# CANTransceiver.net
KiCad netlist of a schematic drawn in Altium Designer
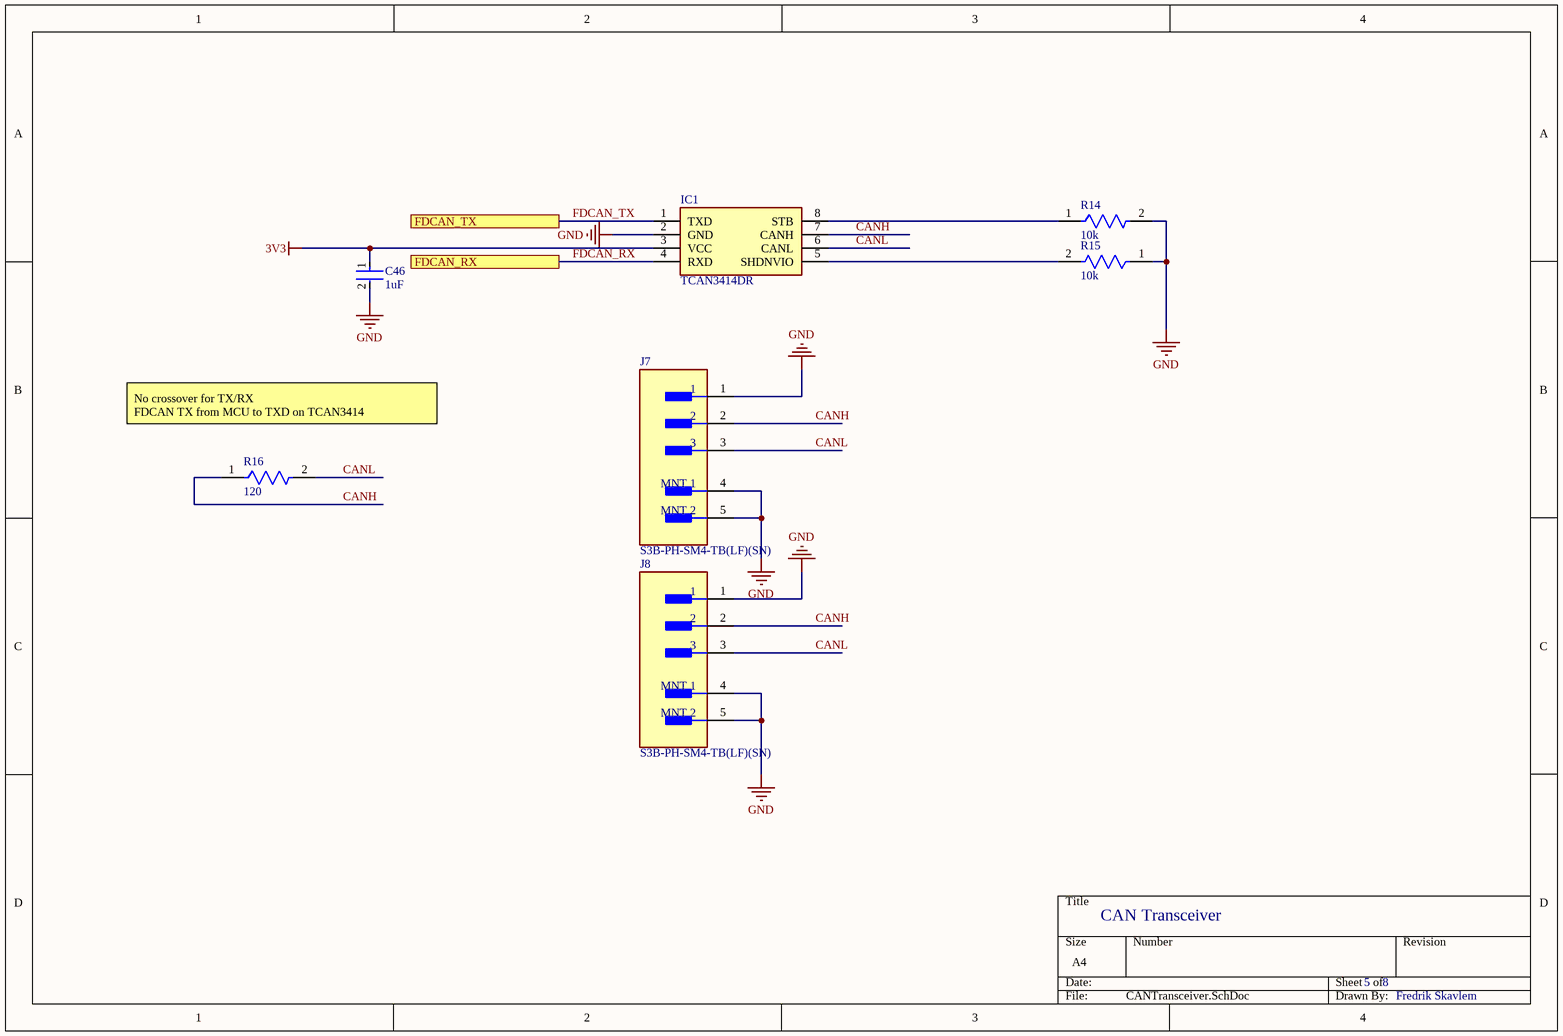
[diagram p0: CANTransceiver.SchDoc]

(export (version "E")
  (design (tool "Eeschema 10.0.6"))
  (components
    (comp (ref "C46")
      (value "1uF")
      (footprint "FP-CL10-IPC_C")
      (description "Cap Ceramic 1uF 16V X7R ±10% Pad SMD 0603 +125°C T/R\r\nCL10B105KO8NNNL")
      (fields (field (name "TOLERANCE") "10%"))
      (libsource (lib "Altium Content Vault") (part "b4654b650e69147ec39a6b967a45e02"))
    )
    (comp (ref "IC1")
      (value "TCAN3414DR")
      (footprint "SamacSys:SOIC127P600X175-8N")
      (description "Integrated Circuit")
      (fields (field (name "MOUSER PART NUMBER") "595-TCAN3414DR"))
      (libsource (lib "*") (part "TCAN3414DR"))
    )
    (comp (ref "J7")
      (value "S3B-PH-SM4-TB(LF)(SN)")
      (footprint "FP-S3B-PH-SM4-TB_LF_SN-MFG")
      (description "Connector Header, PH Series, 3 Position, Side Entry, 2.00mm, Solder, Surface Mount, Natural.")
      (libsource (lib "UiS Aerospace") (part "38689d6f3df0f9b234c6ddcef280d85"))
    )
    (comp (ref "J8")
      (value "S3B-PH-SM4-TB(LF)(SN)")
      (footprint "FP-S3B-PH-SM4-TB_LF_SN-MFG")
      (description "Connector Header, PH Series, 3 Position, Side Entry, 2.00mm, Solder, Surface Mount, Natural.")
      (libsource (lib "UiS Aerospace") (part "38689d6f3df0f9b234c6ddcef280d85"))
    )
    (comp (ref "R14")
      (value "10k")
      (footprint "FP-RT0603-IPC_C")
      (description "RES SMD 10K OHM 1% 1/10W 0603\r\nRT0603FRE0710KL")
      (fields
        (field (name "MANUFACTURER") "Yageo")
        (field (name "OCTOPART") "https://octopart.com/rt0603fre0710kl-yageo-40009243")
      )
      (libsource (lib "Altium Content Vault") (part "1029c3af85768c4190bb7ad29bc67b5"))
    )
    (comp (ref "R15")
      (value "10k")
      (footprint "FP-RT0603-IPC_C")
      (description "RES SMD 10K OHM 1% 1/10W 0603\r\nRT0603FRE0710KL")
      (fields
        (field (name "MANUFACTURER") "Yageo")
        (field (name "OCTOPART") "https://octopart.com/rt0603fre0710kl-yageo-40009243")
      )
      (libsource (lib "Altium Content Vault") (part "1029c3af85768c4190bb7ad29bc67b5"))
    )
    (comp (ref "R16")
      (value "120")
      (footprint "FP-AF0603-IPC_C")
      (description "Anti-Sulfurated Chip Resistors Automotive Grade 120Ω 1% 100ppm/°C 0603 AF0603FR-07120RL")
      (fields (field (name "TOLERANCE") "1%"))
      (libsource (lib "Altium Content Vault") (part "1029c3af85768c4190bb7ad29bc67b5"))
    )
  )
  (nets
    (net (code "1") (name "/CANH") (class "Default")
      (node (ref "IC1") (pin "7") (pinfunction "CANH_7") (pintype "passive"))
      (node (ref "J7") (pin "2") (pinfunction "2_2") (pintype "passive"))
      (node (ref "J8") (pin "2") (pinfunction "2_2") (pintype "passive"))
      (node (ref "R16") (pin "1") (pinfunction "1_1") (pintype "passive"))
    )
    (net (code "2") (name "/CANL") (class "Default")
      (node (ref "IC1") (pin "6") (pinfunction "CANL_6") (pintype "passive"))
      (node (ref "J7") (pin "3") (pinfunction "3_3") (pintype "passive"))
      (node (ref "J8") (pin "3") (pinfunction "3_3") (pintype "passive"))
      (node (ref "R16") (pin "2") (pinfunction "2_2") (pintype "passive"))
    )
    (net (code "3") (name "/FDCAN_RX") (class "Default")
      (node (ref "IC1") (pin "4") (pinfunction "RXD_4") (pintype "passive"))
    )
    (net (code "4") (name "/FDCAN_TX") (class "Default")
      (node (ref "IC1") (pin "1") (pinfunction "TXD_1") (pintype "passive"))
    )
    (net (code "5") (name "3V3") (class "Default")
      (node (ref "C46") (pin "1") (pinfunction "1_1") (pintype "passive"))
      (node (ref "IC1") (pin "3") (pinfunction "VCC_3") (pintype "passive"))
    )
    (net (code "6") (name "GND") (class "Default")
      (node (ref "C46") (pin "2") (pinfunction "2_2") (pintype "passive"))
      (node (ref "IC1") (pin "2") (pinfunction "GND_2") (pintype "passive"))
      (node (ref "J7") (pin "1") (pinfunction "1_1") (pintype "passive"))
      (node (ref "J7") (pin "4") (pinfunction "MNT_1_4") (pintype "passive"))
      (node (ref "J7") (pin "5") (pinfunction "MNT_2_5") (pintype "passive"))
      (node (ref "J8") (pin "1") (pinfunction "1_1") (pintype "passive"))
      (node (ref "J8") (pin "4") (pinfunction "MNT_1_4") (pintype "passive"))
      (node (ref "J8") (pin "5") (pinfunction "MNT_2_5") (pintype "passive"))
      (node (ref "R14") (pin "2") (pinfunction "2_2") (pintype "passive"))
      (node (ref "R15") (pin "1") (pinfunction "1_1") (pintype "passive"))
    )
    (net (code "7") (name "Net-(IC1-SHDNVIO)") (class "Default")
      (node (ref "IC1") (pin "5") (pinfunction "SHDNVIO_5") (pintype "passive"))
      (node (ref "R15") (pin "2") (pinfunction "2_2") (pintype "passive"))
    )
    (net (code "8") (name "Net-(IC1-STB)") (class "Default")
      (node (ref "IC1") (pin "8") (pinfunction "STB_8") (pintype "passive"))
      (node (ref "R14") (pin "1") (pinfunction "1_1") (pintype "passive"))
    )
  )
)
